# Sheet1.net
KiCad netlist of a schematic drawn in Altium Designer
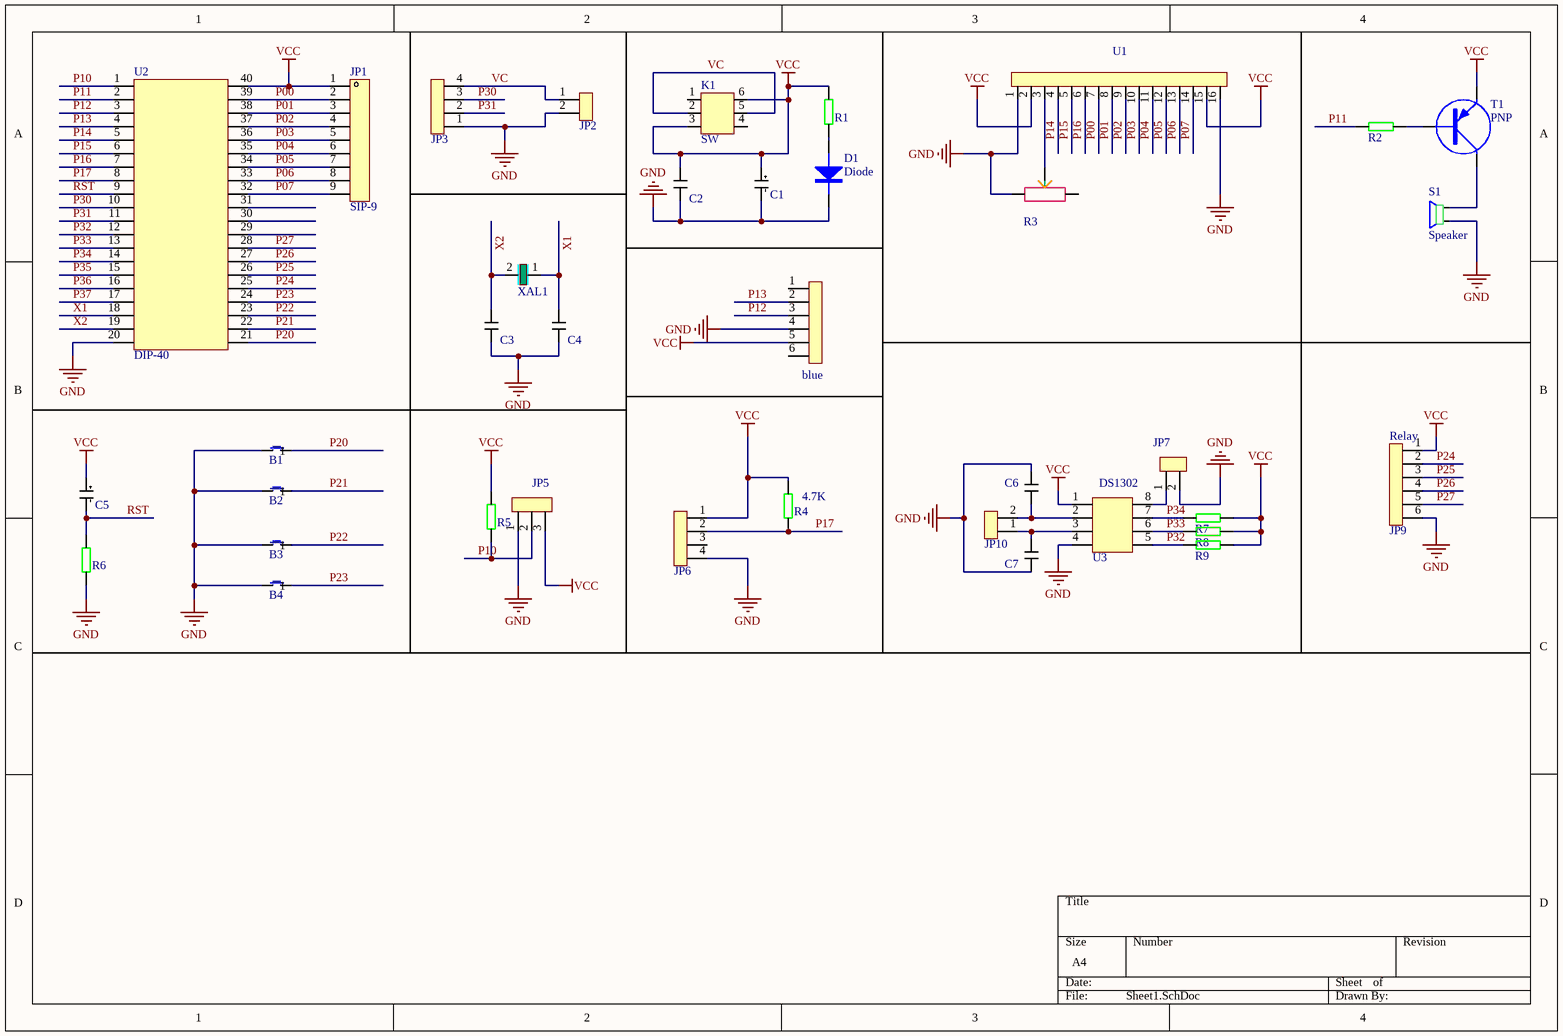
[diagram p0: Sheet1.SchDoc]

(export (version "E")
  (design (tool "Eeschema 10.0.6"))
  (components
    (comp (ref "B1") (value "Button") (footprint "Button") (libsource (lib "集成库") (part "Button")))
    (comp (ref "B2") (value "Button") (footprint "Button") (libsource (lib "集成库") (part "Button")))
    (comp (ref "B3") (value "Button") (footprint "Button") (libsource (lib "集成库") (part "Button")))
    (comp (ref "B4") (value "Button") (footprint "Button") (libsource (lib "集成库") (part "Button")))
    (comp (ref "C1") (value "CAP+") (footprint "CAP-100mil") (libsource (lib "集成库") (part "CAP+")))
    (comp (ref "C2") (value "CAP") (footprint "CAP-100mil") (libsource (lib "集成库") (part "CAP")))
    (comp (ref "C3") (value "CAP") (footprint "0805") (libsource (lib "集成库") (part "CAP")))
    (comp (ref "C4") (value "CAP") (footprint "0805") (libsource (lib "集成库") (part "CAP")))
    (comp (ref "C5") (value "CAP+") (footprint "CAP-100mil") (libsource (lib "集成库") (part "CAP+")))
    (comp (ref "C6") (value "CAP") (footprint "0805") (libsource (lib "集成库") (part "CAP")))
    (comp (ref "C7") (value "CAP") (footprint "0805") (libsource (lib "集成库") (part "CAP")))
    (comp (ref "D1") (value "Diode") (footprint "SIP-2") (libsource (lib "集成库") (part "Diode")))
    (comp (ref "JP1") (value "SIP-9") (footprint "SIP-9") (libsource (lib "集成库") (part "SIP-9")))
    (comp (ref "JP2") (value "SIP-2") (footprint "SIP-2") (libsource (lib "") (part "SIP-2_1")))
    (comp (ref "JP3") (value "SIP-4") (footprint "SIP-4") (libsource (lib "集成库") (part "SIP-4")))
    (comp (ref "JP4") (value "blue") (footprint "SIP-6") (libsource (lib "集成库") (part "SIP-6")))
    (comp (ref "JP5") (value "SIP-3") (footprint "SIP-3") (libsource (lib "集成库") (part "SIP-3")))
    (comp (ref "JP6") (value "SIP-4") (footprint "SIP-4") (libsource (lib "") (part "SIP-4_1")))
    (comp (ref "JP7") (value "SIP-2") (footprint "SIP-6") (libsource (lib "集成库") (part "SIP-2")))
    (comp (ref "JP9") (value "Relay") (footprint "SIP-6") (libsource (lib "") (part "SIP-6_1")))
    (comp (ref "JP10") (value "SIP-2") (footprint "SIP-2") (libsource (lib "") (part "SIP-2_2")))
    (comp (ref "K1") (value "SW") (footprint "SW") (libsource (lib "集成库") (part "SW")))
    (comp (ref "R1") (value "RES") (footprint "0805") (libsource (lib "集成库") (part "RES")))
    (comp (ref "R2") (value "RES") (footprint "0805") (libsource (lib "集成库") (part "RES")))
    (comp (ref "R3") (value "电位器") (footprint "电位器") (libsource (lib "集成库") (part "电位器")))
    (comp (ref "R4")
      (value "RES")
      (footprint "RES-300mil")
      (fields (field (name "ALTIUM_UNNAMED_1") "4.7K"))
      (libsource (lib "集成库") (part "RES"))
    )
    (comp (ref "R5") (value "RES") (footprint "RES-300mil") (libsource (lib "集成库") (part "RES")))
    (comp (ref "R6") (value "RES") (footprint "RES-300mil") (libsource (lib "集成库") (part "RES")))
    (comp (ref "R7") (value "RES") (footprint "0805") (libsource (lib "集成库") (part "RES")))
    (comp (ref "R8") (value "RES") (footprint "0805") (libsource (lib "集成库") (part "RES")))
    (comp (ref "R9") (value "RES") (footprint "0805") (libsource (lib "集成库") (part "RES")))
    (comp (ref "S1") (value "Speaker") (footprint "RES-300mil") (libsource (lib "集成库") (part "Speaker")))
    (comp (ref "T1") (value "PNP") (footprint "三极管") (libsource (lib "集成库") (part "PNP")))
    (comp (ref "U1") (value "SIP-16") (footprint "SIP-16") (libsource (lib "集成库") (part "SIP-16")))
    (comp (ref "U2") (value "DIP-40") (footprint "DIP-40-600mil") (libsource (lib "集成库") (part "DIP-40")))
    (comp (ref "U3") (value "DS1302") (footprint "SOP8") (libsource (lib "集成库") (part "DIP-8")))
    (comp (ref "XAL1") (value "晶振") (footprint "晶振-200mil") (libsource (lib "集成库") (part "晶振")))
  )
  (nets
    (net (code "1") (name "/P00") (class "Default")
      (node (ref "JP1") (pin "2") (pinfunction "2_2") (pintype "passive"))
      (node (ref "U1") (pin "7") (pinfunction "7_7") (pintype "passive"))
      (node (ref "U2") (pin "39") (pinfunction "39_39") (pintype "passive"))
    )
    (net (code "2") (name "/P01") (class "Default")
      (node (ref "JP1") (pin "3") (pinfunction "3_3") (pintype "passive"))
      (node (ref "U1") (pin "8") (pinfunction "8_8") (pintype "passive"))
      (node (ref "U2") (pin "38") (pinfunction "38_38") (pintype "passive"))
    )
    (net (code "3") (name "/P02") (class "Default")
      (node (ref "JP1") (pin "4") (pinfunction "4_4") (pintype "passive"))
      (node (ref "U1") (pin "9") (pinfunction "9_9") (pintype "passive"))
      (node (ref "U2") (pin "37") (pinfunction "37_37") (pintype "passive"))
    )
    (net (code "4") (name "/P03") (class "Default")
      (node (ref "JP1") (pin "5") (pinfunction "5_5") (pintype "passive"))
      (node (ref "U1") (pin "10") (pinfunction "10_10") (pintype "passive"))
      (node (ref "U2") (pin "36") (pinfunction "36_36") (pintype "passive"))
    )
    (net (code "5") (name "/P04") (class "Default")
      (node (ref "JP1") (pin "6") (pinfunction "6_6") (pintype "passive"))
      (node (ref "U1") (pin "11") (pinfunction "11_11") (pintype "passive"))
      (node (ref "U2") (pin "35") (pinfunction "35_35") (pintype "passive"))
    )
    (net (code "6") (name "/P05") (class "Default")
      (node (ref "JP1") (pin "7") (pinfunction "7_7") (pintype "passive"))
      (node (ref "U1") (pin "12") (pinfunction "12_12") (pintype "passive"))
      (node (ref "U2") (pin "34") (pinfunction "34_34") (pintype "passive"))
    )
    (net (code "7") (name "/P06") (class "Default")
      (node (ref "JP1") (pin "8") (pinfunction "8_8") (pintype "passive"))
      (node (ref "U1") (pin "13") (pinfunction "13_13") (pintype "passive"))
      (node (ref "U2") (pin "33") (pinfunction "33_33") (pintype "passive"))
    )
    (net (code "8") (name "/P07") (class "Default")
      (node (ref "JP1") (pin "9") (pinfunction "9_9") (pintype "passive"))
      (node (ref "U1") (pin "14") (pinfunction "14_14") (pintype "passive"))
      (node (ref "U2") (pin "32") (pinfunction "32_32") (pintype "passive"))
    )
    (net (code "9") (name "/P10") (class "Default")
      (node (ref "JP5") (pin "2") (pinfunction "2_2") (pintype "passive"))
      (node (ref "R5") (pin "1") (pinfunction "1_1") (pintype "passive"))
      (node (ref "U2") (pin "1") (pinfunction "1_1") (pintype "passive"))
    )
    (net (code "10") (name "/P11") (class "Default")
      (node (ref "R2") (pin "1") (pinfunction "1_1") (pintype "passive"))
      (node (ref "U2") (pin "2") (pinfunction "2_2") (pintype "passive"))
    )
    (net (code "11") (name "/P12") (class "Default")
      (node (ref "JP4") (pin "3") (pinfunction "3_3") (pintype "passive"))
      (node (ref "U2") (pin "3") (pinfunction "3_3") (pintype "passive"))
    )
    (net (code "12") (name "/P13") (class "Default")
      (node (ref "JP4") (pin "2") (pinfunction "2_2") (pintype "passive"))
      (node (ref "U2") (pin "4") (pinfunction "4_4") (pintype "passive"))
    )
    (net (code "13") (name "/P14") (class "Default")
      (node (ref "U1") (pin "4") (pinfunction "4_4") (pintype "passive"))
      (node (ref "U2") (pin "5") (pinfunction "5_5") (pintype "passive"))
    )
    (net (code "14") (name "/P15") (class "Default")
      (node (ref "U1") (pin "5") (pinfunction "5_5") (pintype "passive"))
      (node (ref "U2") (pin "6") (pinfunction "6_6") (pintype "passive"))
    )
    (net (code "15") (name "/P16") (class "Default")
      (node (ref "U1") (pin "6") (pinfunction "6_6") (pintype "passive"))
      (node (ref "U2") (pin "7") (pinfunction "7_7") (pintype "passive"))
    )
    (net (code "16") (name "/P17") (class "Default")
      (node (ref "JP6") (pin "2") (pinfunction "2_2") (pintype "passive"))
      (node (ref "R4") (pin "1") (pinfunction "1_1") (pintype "passive"))
      (node (ref "U2") (pin "8") (pinfunction "8_8") (pintype "passive"))
    )
    (net (code "17") (name "/P20") (class "Default")
      (node (ref "B1") (pin "3") (pinfunction "3_3") (pintype "passive"))
      (node (ref "U2") (pin "21") (pinfunction "21_21") (pintype "passive"))
    )
    (net (code "18") (name "/P21") (class "Default")
      (node (ref "B2") (pin "3") (pinfunction "3_3") (pintype "passive"))
      (node (ref "U2") (pin "22") (pinfunction "22_22") (pintype "passive"))
    )
    (net (code "19") (name "/P22") (class "Default")
      (node (ref "B3") (pin "3") (pinfunction "3_3") (pintype "passive"))
      (node (ref "U2") (pin "23") (pinfunction "23_23") (pintype "passive"))
    )
    (net (code "20") (name "/P23") (class "Default")
      (node (ref "B4") (pin "3") (pinfunction "3_3") (pintype "passive"))
      (node (ref "U2") (pin "24") (pinfunction "24_24") (pintype "passive"))
    )
    (net (code "21") (name "/P24") (class "Default")
      (node (ref "JP9") (pin "2") (pinfunction "2_2") (pintype "passive"))
      (node (ref "U2") (pin "25") (pinfunction "25_25") (pintype "passive"))
    )
    (net (code "22") (name "/P25") (class "Default")
      (node (ref "JP9") (pin "3") (pinfunction "3_3") (pintype "passive"))
      (node (ref "U2") (pin "26") (pinfunction "26_26") (pintype "passive"))
    )
    (net (code "23") (name "/P26") (class "Default")
      (node (ref "JP9") (pin "4") (pinfunction "4_4") (pintype "passive"))
      (node (ref "U2") (pin "27") (pinfunction "27_27") (pintype "passive"))
    )
    (net (code "24") (name "/P27") (class "Default")
      (node (ref "JP9") (pin "5") (pinfunction "5_5") (pintype "passive"))
      (node (ref "U2") (pin "28") (pinfunction "28_28") (pintype "passive"))
    )
    (net (code "25") (name "/P30") (class "Default")
      (node (ref "JP3") (pin "3") (pinfunction "3_3") (pintype "passive"))
      (node (ref "U2") (pin "10") (pinfunction "10_10") (pintype "passive"))
    )
    (net (code "26") (name "/P31") (class "Default")
      (node (ref "JP3") (pin "2") (pinfunction "2_2") (pintype "passive"))
      (node (ref "U2") (pin "11") (pinfunction "11_11") (pintype "passive"))
    )
    (net (code "27") (name "/P32") (class "Default")
      (node (ref "R9") (pin "1") (pinfunction "1_1") (pintype "passive"))
      (node (ref "U2") (pin "12") (pinfunction "12_12") (pintype "passive"))
      (node (ref "U3") (pin "5") (pinfunction "5_5") (pintype "passive"))
    )
    (net (code "28") (name "/P33") (class "Default")
      (node (ref "R8") (pin "1") (pinfunction "1_1") (pintype "passive"))
      (node (ref "U2") (pin "13") (pinfunction "13_13") (pintype "passive"))
      (node (ref "U3") (pin "6") (pinfunction "6_6") (pintype "passive"))
    )
    (net (code "29") (name "/P34") (class "Default")
      (node (ref "R7") (pin "1") (pinfunction "1_1") (pintype "passive"))
      (node (ref "U2") (pin "14") (pinfunction "14_14") (pintype "passive"))
      (node (ref "U3") (pin "7") (pinfunction "7_7") (pintype "passive"))
    )
    (net (code "30") (name "/P35") (class "Default")
      (node (ref "U2") (pin "15") (pinfunction "15_15") (pintype "passive"))
    )
    (net (code "31") (name "/P36") (class "Default")
      (node (ref "U2") (pin "16") (pinfunction "16_16") (pintype "passive"))
    )
    (net (code "32") (name "/P37") (class "Default")
      (node (ref "U2") (pin "17") (pinfunction "17_17") (pintype "passive"))
    )
    (net (code "33") (name "/RST") (class "Default")
      (node (ref "C5") (pin "2") (pinfunction "2_2") (pintype "passive"))
      (node (ref "R6") (pin "2") (pinfunction "2_2") (pintype "passive"))
      (node (ref "U2") (pin "9") (pinfunction "9_9") (pintype "passive"))
    )
    (net (code "34") (name "/VC") (class "Default")
      (node (ref "JP2") (pin "1") (pinfunction "1_1") (pintype "passive"))
      (node (ref "JP3") (pin "4") (pinfunction "4_4") (pintype "passive"))
      (node (ref "K1") (pin "2") (pinfunction "2_2") (pintype "passive"))
      (node (ref "K1") (pin "5") (pinfunction "5_5") (pintype "passive"))
    )
    (net (code "35") (name "/X1") (class "Default")
      (node (ref "C4") (pin "1") (pinfunction "1_1") (pintype "passive"))
      (node (ref "U2") (pin "18") (pinfunction "18_18") (pintype "passive"))
      (node (ref "XAL1") (pin "1") (pinfunction "1_1") (pintype "passive"))
    )
    (net (code "36") (name "/X2") (class "Default")
      (node (ref "C3") (pin "1") (pinfunction "1_1") (pintype "passive"))
      (node (ref "U2") (pin "19") (pinfunction "19_19") (pintype "passive"))
      (node (ref "XAL1") (pin "2") (pinfunction "2_2") (pintype "passive"))
    )
    (net (code "37") (name "GND") (class "Default")
      (node (ref "B1") (pin "1") (pinfunction "1_1") (pintype "passive"))
      (node (ref "B2") (pin "1") (pinfunction "1_1") (pintype "passive"))
      (node (ref "B3") (pin "1") (pinfunction "1_1") (pintype "passive"))
      (node (ref "B4") (pin "1") (pinfunction "1_1") (pintype "passive"))
      (node (ref "C1") (pin "2") (pinfunction "2_2") (pintype "passive"))
      (node (ref "C2") (pin "1") (pinfunction "1_1") (pintype "passive"))
      (node (ref "C3") (pin "2") (pinfunction "2_2") (pintype "passive"))
      (node (ref "C4") (pin "2") (pinfunction "2_2") (pintype "passive"))
      (node (ref "C6") (pin "1") (pinfunction "1_1") (pintype "passive"))
      (node (ref "C7") (pin "1") (pinfunction "1_1") (pintype "passive"))
      (node (ref "D1") (pin "2") (pinfunction "2_2") (pintype "passive"))
      (node (ref "JP2") (pin "2") (pinfunction "2_2") (pintype "passive"))
      (node (ref "JP3") (pin "1") (pinfunction "1_1") (pintype "passive"))
      (node (ref "JP4") (pin "4") (pinfunction "4_4") (pintype "passive"))
      (node (ref "JP5") (pin "1") (pinfunction "1_1") (pintype "passive"))
      (node (ref "JP6") (pin "4") (pinfunction "4_4") (pintype "passive"))
      (node (ref "JP7") (pin "2") (pinfunction "2_2") (pintype "passive"))
      (node (ref "JP9") (pin "6") (pinfunction "6_6") (pintype "passive"))
      (node (ref "R3") (pin "1") (pinfunction "1_1") (pintype "passive"))
      (node (ref "R6") (pin "1") (pinfunction "1_1") (pintype "passive"))
      (node (ref "S1") (pin "1") (pinfunction "1_1") (pintype "passive"))
      (node (ref "U1") (pin "1") (pinfunction "1_1") (pintype "passive"))
      (node (ref "U1") (pin "16") (pinfunction "16_16") (pintype "passive"))
      (node (ref "U2") (pin "20") (pinfunction "20_20") (pintype "passive"))
      (node (ref "U3") (pin "4") (pinfunction "4_4") (pintype "passive"))
    )
    (net (code "38") (name "Net-(C6-Pad2)") (class "Default")
      (node (ref "C6") (pin "2") (pinfunction "2_2") (pintype "passive"))
      (node (ref "JP10") (pin "2") (pinfunction "2_2") (pintype "passive"))
      (node (ref "U3") (pin "2") (pinfunction "2_2") (pintype "passive"))
    )
    (net (code "39") (name "Net-(C7-Pad2)") (class "Default")
      (node (ref "C7") (pin "2") (pinfunction "2_2") (pintype "passive"))
      (node (ref "JP10") (pin "1") (pinfunction "1_1") (pintype "passive"))
      (node (ref "U3") (pin "3") (pinfunction "3_3") (pintype "passive"))
    )
    (net (code "40") (name "Net-(D1-Pad1)") (class "Default")
      (node (ref "D1") (pin "1") (pinfunction "1_1") (pintype "passive"))
      (node (ref "R1") (pin "1") (pinfunction "1_1") (pintype "passive"))
    )
    (net (code "41") (name "Net-(JP7-Pad1)") (class "Default")
      (node (ref "JP7") (pin "1") (pinfunction "1_1") (pintype "passive"))
      (node (ref "U3") (pin "8") (pinfunction "8_8") (pintype "passive"))
    )
    (net (code "42") (name "Net-(R2-Pad2)") (class "Default")
      (node (ref "R2") (pin "2") (pinfunction "2_2") (pintype "passive"))
      (node (ref "T1") (pin "B") (pinfunction "B_B") (pintype "passive"))
    )
    (net (code "43") (name "Net-(R3-Pad2)") (class "Default")
      (node (ref "R3") (pin "2") (pinfunction "2_2") (pintype "passive"))
      (node (ref "U1") (pin "3") (pinfunction "3_3") (pintype "passive"))
    )
    (net (code "44") (name "Net-(S1-Pad2)") (class "Default")
      (node (ref "S1") (pin "2") (pinfunction "2_2") (pintype "passive"))
      (node (ref "T1") (pin "C") (pinfunction "C_C") (pintype "passive"))
    )
    (net (code "45") (name "VCC") (class "Default")
      (node (ref "C1") (pin "1") (pinfunction "1_1") (pintype "passive"))
      (node (ref "C2") (pin "2") (pinfunction "2_2") (pintype "passive"))
      (node (ref "C5") (pin "1") (pinfunction "1_1") (pintype "passive"))
      (node (ref "JP1") (pin "1") (pinfunction "1_1") (pintype "passive"))
      (node (ref "JP4") (pin "5") (pinfunction "5_5") (pintype "passive"))
      (node (ref "JP5") (pin "3") (pinfunction "3_3") (pintype "passive"))
      (node (ref "JP6") (pin "1") (pinfunction "1_1") (pintype "passive"))
      (node (ref "JP9") (pin "1") (pinfunction "1_1") (pintype "passive"))
      (node (ref "K1") (pin "3") (pinfunction "3_3") (pintype "passive"))
      (node (ref "K1") (pin "6") (pinfunction "6_6") (pintype "passive"))
      (node (ref "R1") (pin "2") (pinfunction "2_2") (pintype "passive"))
      (node (ref "R4") (pin "2") (pinfunction "2_2") (pintype "passive"))
      (node (ref "R5") (pin "2") (pinfunction "2_2") (pintype "passive"))
      (node (ref "R7") (pin "2") (pinfunction "2_2") (pintype "passive"))
      (node (ref "R8") (pin "2") (pinfunction "2_2") (pintype "passive"))
      (node (ref "R9") (pin "2") (pinfunction "2_2") (pintype "passive"))
      (node (ref "T1") (pin "E") (pinfunction "E_E") (pintype "passive"))
      (node (ref "U1") (pin "15") (pinfunction "15_15") (pintype "passive"))
      (node (ref "U1") (pin "2") (pinfunction "2_2") (pintype "passive"))
      (node (ref "U2") (pin "40") (pinfunction "40_40") (pintype "passive"))
      (node (ref "U3") (pin "1") (pinfunction "1_1") (pintype "passive"))
    )
    (net (code "46") (name "unconnected-(JP4-Pad1)") (class "Default")
      (node (ref "JP4") (pin "1") (pinfunction "1_1") (pintype "passive"))
    )
    (net (code "47") (name "unconnected-(JP4-Pad6)") (class "Default")
      (node (ref "JP4") (pin "6") (pinfunction "6_6") (pintype "passive"))
    )
    (net (code "48") (name "unconnected-(JP6-Pad3)") (class "Default")
      (node (ref "JP6") (pin "3") (pinfunction "3_3") (pintype "passive"))
    )
    (net (code "49") (name "unconnected-(K1-Pad1)") (class "Default")
      (node (ref "K1") (pin "1") (pinfunction "1_1") (pintype "passive"))
    )
    (net (code "50") (name "unconnected-(K1-Pad4)") (class "Default")
      (node (ref "K1") (pin "4") (pinfunction "4_4") (pintype "passive"))
    )
    (net (code "51") (name "unconnected-(R3-Pad3)") (class "Default")
      (node (ref "R3") (pin "3") (pinfunction "3_3") (pintype "passive"))
    )
    (net (code "52") (name "unconnected-(U2-Pad29)") (class "Default")
      (node (ref "U2") (pin "29") (pinfunction "29_29") (pintype "passive"))
    )
    (net (code "53") (name "unconnected-(U2-Pad30)") (class "Default")
      (node (ref "U2") (pin "30") (pinfunction "30_30") (pintype "passive"))
    )
    (net (code "54") (name "unconnected-(U2-Pad31)") (class "Default")
      (node (ref "U2") (pin "31") (pinfunction "31_31") (pintype "passive"))
    )
  )
)
